# Single-Phase-Energy-Meter_v1_3-rev2.net
KiCad netlist of a schematic drawn in EAGLE
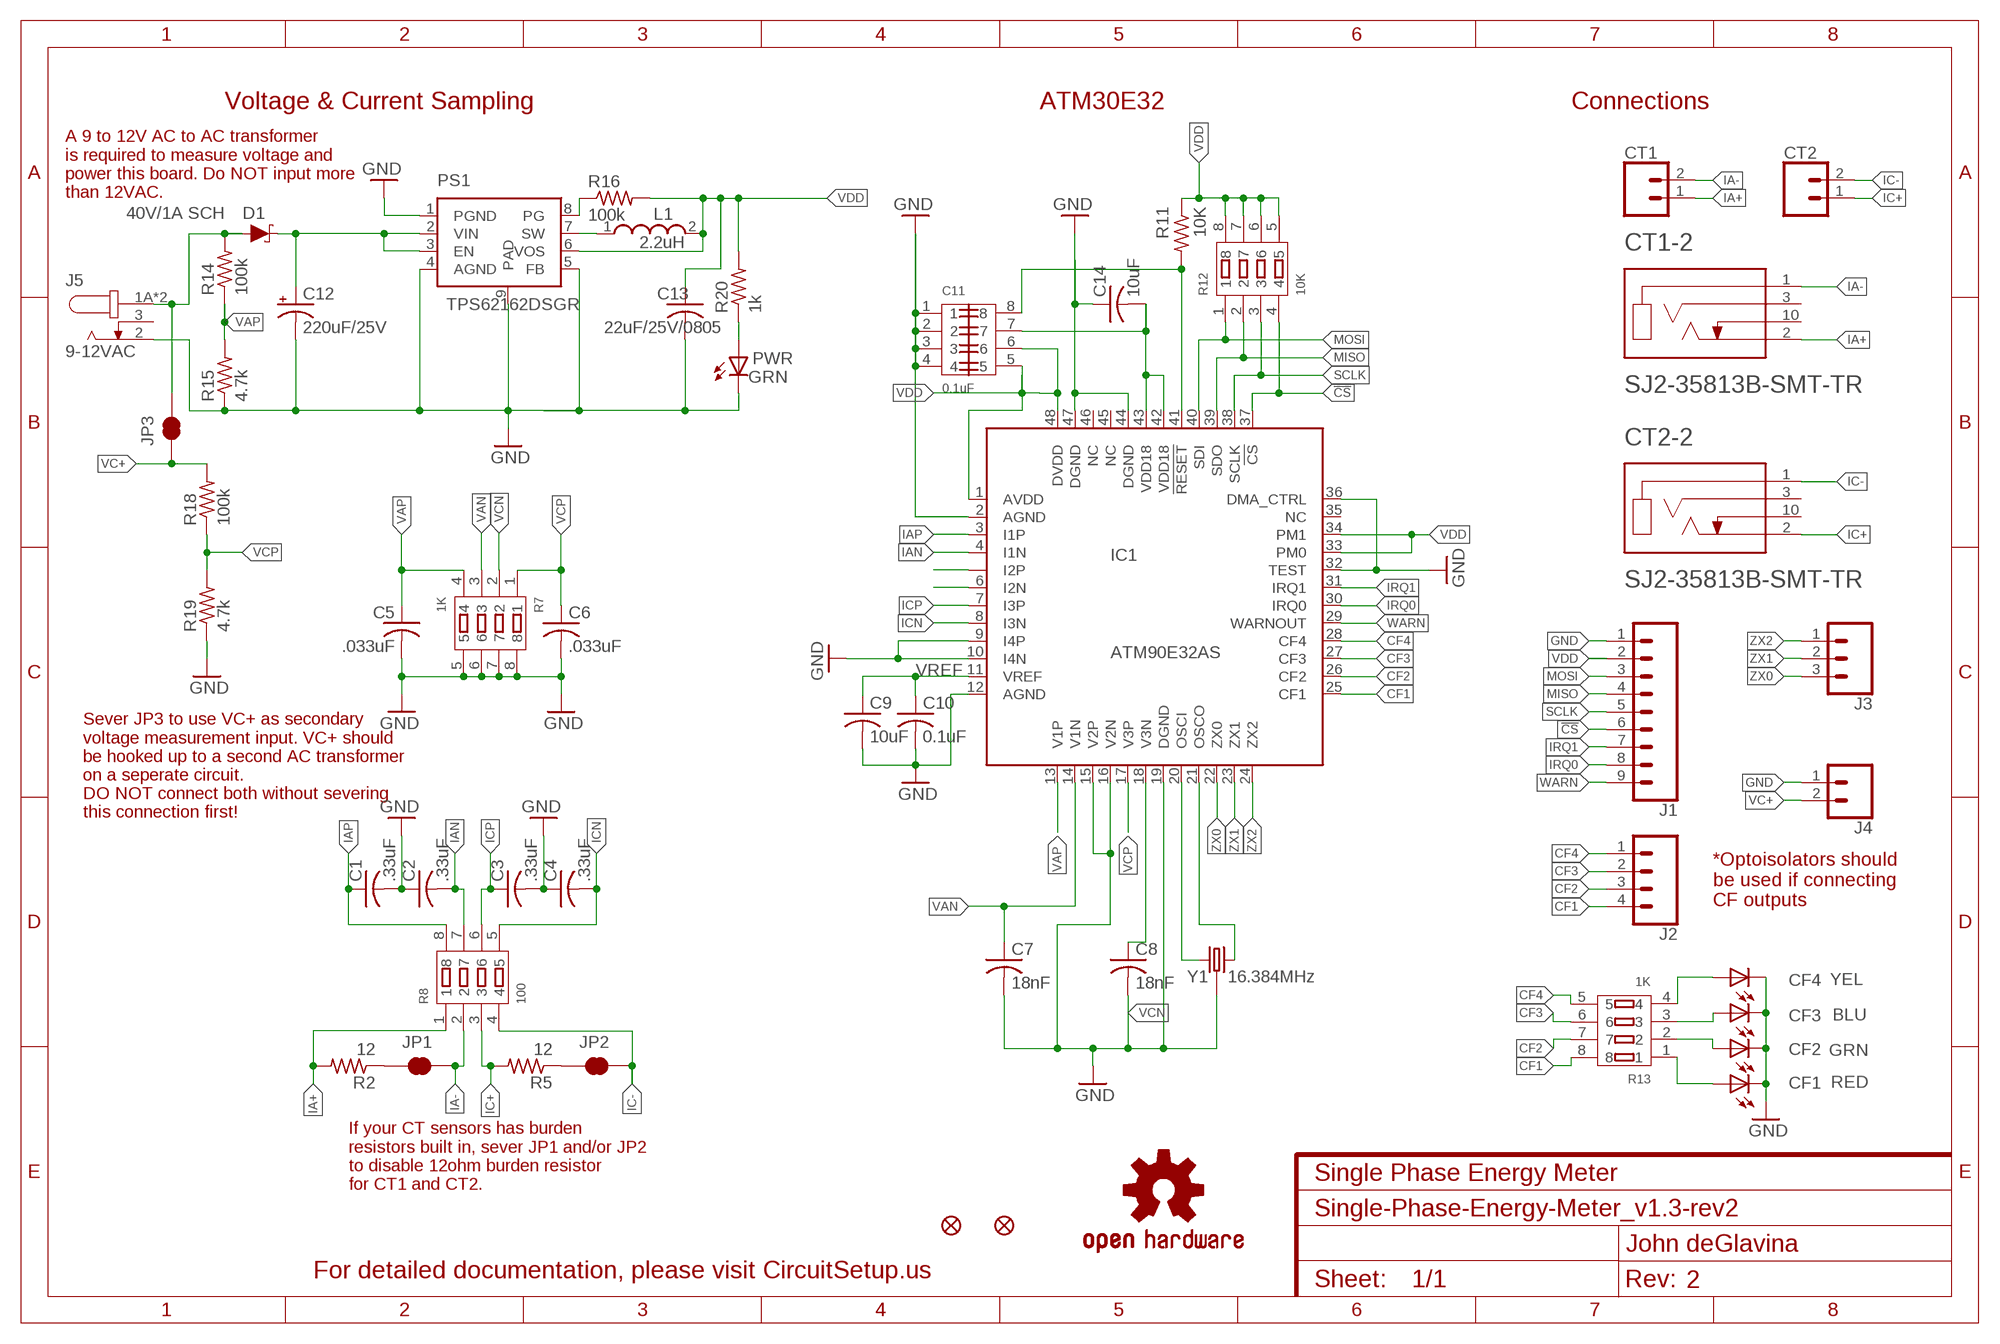
[diagram p0: schematic, sheet 1]

(export (version "E")
  (design (tool "Eeschema 10.0.6"))
  (components
    (comp (ref "C1")
      (value ".33uF")
      (footprint "eagle-import:C0603")
      (libsource (lib "eagle-import") (part "C-USC0603"))
    )
    (comp (ref "C2")
      (value ".33uF")
      (footprint "eagle-import:C0603")
      (libsource (lib "eagle-import") (part "C-USC0603"))
    )
    (comp (ref "C3")
      (value ".33uF")
      (footprint "eagle-import:C0603")
      (libsource (lib "eagle-import") (part "C-USC0603"))
    )
    (comp (ref "C4")
      (value ".33uF")
      (footprint "eagle-import:C0603")
      (libsource (lib "eagle-import") (part "C-USC0603"))
    )
    (comp (ref "C5")
      (value ".033uF")
      (footprint "eagle-import:C0603")
      (libsource (lib "eagle-import") (part "C-USC0603"))
    )
    (comp (ref "C6")
      (value ".033uF")
      (footprint "eagle-import:C0603")
      (libsource (lib "eagle-import") (part "C-USC0603"))
    )
    (comp (ref "C7")
      (value "18nF")
      (footprint "eagle-import:C0603")
      (libsource (lib "eagle-import") (part "C-USC0603"))
    )
    (comp (ref "C8")
      (value "18nF")
      (footprint "eagle-import:C0603")
      (libsource (lib "eagle-import") (part "C-USC0603"))
    )
    (comp (ref "C9")
      (value "10uF")
      (footprint "eagle-import:C0603")
      (libsource (lib "eagle-import") (part "C-USC0603"))
    )
    (comp (ref "C10")
      (value "0.1uF")
      (footprint "eagle-import:C0603")
      (libsource (lib "eagle-import") (part "C-USC0603"))
    )
    (comp (ref "C11")
      (value "0.1uF")
      (footprint "eagle-import:CAPCAF80P320X160X70-8")
      (libsource (lib "eagle-import") (part "CAP-ARRAY4"))
    )
    (comp (ref "C12")
      (value "220uF/25V")
      (footprint "eagle-import:153CLV-0605")
      (libsource (lib "eagle-import") (part "CPOL-US153CLV-0605"))
    )
    (comp (ref "C13")
      (value "22uF/25V/0805")
      (footprint "eagle-import:C0805")
      (libsource (lib "eagle-import") (part "C-USC0805"))
    )
    (comp (ref "C14")
      (value "10uF")
      (footprint "eagle-import:C0603")
      (libsource (lib "eagle-import") (part "C-USC0603"))
    )
    (comp (ref "CF1")
      (value "RED")
      (footprint "eagle-import:CHIP-LED0603")
      (libsource (lib "eagle-import") (part "LEDCHIP-LED0603"))
    )
    (comp (ref "CF2")
      (value "GRN")
      (footprint "eagle-import:CHIP-LED0603")
      (libsource (lib "eagle-import") (part "LEDCHIP-LED0603"))
    )
    (comp (ref "CF3")
      (value "BLU")
      (footprint "eagle-import:CHIP-LED0603")
      (libsource (lib "eagle-import") (part "LEDCHIP-LED0603"))
    )
    (comp (ref "CF4")
      (value "YEL")
      (footprint "eagle-import:CHIP-LED0603")
      (libsource (lib "eagle-import") (part "LEDCHIP-LED0603"))
    )
    (comp (ref "CT1")
      (value "CONN_023.5MM")
      (footprint "eagle-import:SCREWTERMINAL-3.5MM-2")
      (libsource (lib "eagle-import") (part "CONN_023.5MM"))
    )
    (comp (ref "CT1-2")
      (value "SJ2-35813B-SMT-TR")
      (footprint "eagle-import:CUI_SJ2-35813B-SMT-TR")
      (fields (field (name "MANUFACTURER") "CUI"))
      (libsource (lib "eagle-import") (part "SJ2-35813B-SMT-TR"))
    )
    (comp (ref "CT2")
      (value "CONN_023.5MM")
      (footprint "eagle-import:SCREWTERMINAL-3.5MM-2")
      (libsource (lib "eagle-import") (part "CONN_023.5MM"))
    )
    (comp (ref "CT2-2")
      (value "SJ2-35813B-SMT-TR")
      (footprint "eagle-import:CUI_SJ2-35813B-SMT-TR")
      (fields (field (name "MANUFACTURER") "CUI"))
      (libsource (lib "eagle-import") (part "SJ2-35813B-SMT-TR"))
    )
    (comp (ref "D1")
      (value "40V/1A SCH")
      (footprint "eagle-import:SMA-DIODE")
      (libsource (lib "eagle-import") (part "DIODE-SCHOTTKY-SS14"))
    )
    (comp (ref "FD1")
      (value "FIDUCIALUFIDUCIAL")
      (footprint "eagle-import:FIDUCIAL-MICRO")
      (libsource (lib "eagle-import") (part "FIDUCIALUFIDUCIAL"))
    )
    (comp (ref "FD2")
      (value "FIDUCIALUFIDUCIAL")
      (footprint "eagle-import:FIDUCIAL-MICRO")
      (libsource (lib "eagle-import") (part "FIDUCIALUFIDUCIAL"))
    )
    (comp (ref "IC1")
      (value "ATM90E32AS")
      (footprint "eagle-import:QFP50P900X900X120-48N")
      (fields (field (name "SPICEPREFIX") "X"))
      (libsource (lib "eagle-import") (part "ATM90E36"))
    )
    (comp (ref "J1")
      (value "CONN_09")
      (footprint "eagle-import:1X09")
      (libsource (lib "eagle-import") (part "CONN_09"))
    )
    (comp (ref "J2")
      (value "CONN_04")
      (footprint "eagle-import:1X04")
      (libsource (lib "eagle-import") (part "CONN_04"))
    )
    (comp (ref "J3")
      (value "CONN_03")
      (footprint "eagle-import:1X03")
      (libsource (lib "eagle-import") (part "CONN_03"))
    )
    (comp (ref "J4")
      (value "CONN_02")
      (footprint "eagle-import:1X02")
      (libsource (lib "eagle-import") (part "CONN_02"))
    )
    (comp (ref "J5")
      (value "9-12VAC")
      (footprint "eagle-import:CUI_PJ-002AH-SMT-TR")
      (fields (field (name "MF") "CUI") (field (name "MP") "PJ-002AH-SMT-TR"))
      (libsource (lib "eagle-import") (part "PJ-002AH-SMT-TR"))
    )
    (comp (ref "JP1")
      (value "JUMPER-SMT_2_NC_TRACE_SILK")
      (footprint "eagle-import:SMT-JUMPER_2_NC_TRACE_SILK")
      (libsource (lib "eagle-import") (part "JUMPER-SMT_2_NC_TRACE_SILK"))
    )
    (comp (ref "JP2")
      (value "JUMPER-SMT_2_NC_TRACE_SILK")
      (footprint "eagle-import:SMT-JUMPER_2_NC_TRACE_SILK")
      (libsource (lib "eagle-import") (part "JUMPER-SMT_2_NC_TRACE_SILK"))
    )
    (comp (ref "JP3")
      (value "JUMPER-SMT_2_NC_TRACE_SILK")
      (footprint "eagle-import:SMT-JUMPER_2_NC_TRACE_SILK")
      (libsource (lib "eagle-import") (part "JUMPER-SMT_2_NC_TRACE_SILK"))
    )
    (comp (ref "L1")
      (value "2.2uH")
      (footprint "eagle-import:INDPM4042X200N")
      (fields (field (name "ARROW_PART_NUMBER") "PA4332.222NLT"))
      (libsource (lib "eagle-import") (part "PA4332.222NLT"))
    )
    (comp (ref "LOGO1")
      (value "OSHW-LOGOS")
      (footprint "eagle-import:OSHW-LOGO-S")
      (libsource (lib "eagle-import") (part "OSHW-LOGOS"))
    )
    (comp (ref "PS1")
      (value "TPS62162DSGR")
      (footprint "eagle-import:SON50P200X200X80-9N")
      (libsource (lib "eagle-import") (part "TPS62162DSGR"))
    )
    (comp (ref "PWR")
      (value "GRN")
      (footprint "eagle-import:CHIP-LED0603")
      (libsource (lib "eagle-import") (part "LEDCHIP-LED0603"))
    )
    (comp (ref "R2")
      (value "12")
      (footprint "eagle-import:R0603")
      (libsource (lib "eagle-import") (part "R-US_R0603"))
    )
    (comp (ref "R5")
      (value "12")
      (footprint "eagle-import:R0603")
      (libsource (lib "eagle-import") (part "R-US_R0603"))
    )
    (comp (ref "R7")
      (value "1K")
      (footprint "eagle-import:RA1206-8")
      (fields (field (name "MPN") "Chip-Array-Series-1%"))
      (libsource (lib "eagle-import") (part "SMD-RES-ARRAY-1K-4R(RA1206-8)"))
    )
    (comp (ref "R8")
      (value "100")
      (footprint "eagle-import:RA1206-8")
      (fields (field (name "MPN") "Chip-Array-Series-1%"))
      (libsource (lib "eagle-import") (part "SMD-RES-ARRAY-1K-4R(RA1206-8)"))
    )
    (comp (ref "R11")
      (value "10K")
      (footprint "eagle-import:R0603")
      (libsource (lib "eagle-import") (part "R-US_R0603"))
    )
    (comp (ref "R12")
      (value "10K")
      (footprint "eagle-import:RA1206-8")
      (fields (field (name "MPN") "Chip-Array-Series-1%"))
      (libsource (lib "eagle-import") (part "SMD-RES-ARRAY-1K-4R(RA1206-8)"))
    )
    (comp (ref "R13")
      (value "1K")
      (footprint "eagle-import:RA1206-8")
      (fields (field (name "MPN") "Chip-Array-Series-1%"))
      (libsource (lib "eagle-import") (part "SMD-RES-ARRAY-1K-4R(RA1206-8)"))
    )
    (comp (ref "R14")
      (value "100k")
      (footprint "eagle-import:R0603")
      (libsource (lib "eagle-import") (part "R-US_R0603"))
    )
    (comp (ref "R15")
      (value "4.7k")
      (footprint "eagle-import:R0603")
      (libsource (lib "eagle-import") (part "R-US_R0603"))
    )
    (comp (ref "R16")
      (value "100k")
      (footprint "eagle-import:R0603")
      (libsource (lib "eagle-import") (part "R-US_R0603"))
    )
    (comp (ref "R18")
      (value "100k")
      (footprint "eagle-import:R0603")
      (libsource (lib "eagle-import") (part "R-US_R0603"))
    )
    (comp (ref "R19")
      (value "4.7k")
      (footprint "eagle-import:R0603")
      (libsource (lib "eagle-import") (part "R-US_R0603"))
    )
    (comp (ref "R20")
      (value "1k")
      (footprint "eagle-import:R0603")
      (libsource (lib "eagle-import") (part "R-US_R0603"))
    )
    (comp (ref "Y1")
      (value "16.384MHz")
      (footprint "eagle-import:CRYSTAL-SMD-3.2X2.5MM")
      (libsource (lib "eagle-import") (part "CRYSTAL-GROUNDEDSMD-3.2X2.5"))
    )
  )
  (nets
    (net (code "1") (name "/VREF") (class "Default")
      (node (ref "C10") (pin "1") (pinfunction "1_1") (pintype "passive"))
      (node (ref "C9") (pin "1") (pinfunction "1_1") (pintype "passive"))
      (node (ref "IC1") (pin "11") (pinfunction "VREF_11") (pintype "bidirectional"))
    )
    (net (code "2") (name "/~{CS}") (class "Default")
      (node (ref "IC1") (pin "37") (pinfunction "~{CS}_37") (pintype "input"))
      (node (ref "J1") (pin "6") (pinfunction "6_6") (pintype "passive"))
      (node (ref "R12") (pin "4") (pinfunction "4_4") (pintype "bidirectional"))
    )
    (net (code "3") (name "CF1") (class "Default")
      (node (ref "IC1") (pin "25") (pinfunction "CF1_25") (pintype "output"))
      (node (ref "J2") (pin "4") (pinfunction "4_4") (pintype "passive"))
      (node (ref "R13") (pin "8") (pinfunction "8_8") (pintype "bidirectional"))
    )
    (net (code "4") (name "CF2") (class "Default")
      (node (ref "IC1") (pin "26") (pinfunction "CF2_26") (pintype "output"))
      (node (ref "J2") (pin "3") (pinfunction "3_3") (pintype "passive"))
      (node (ref "R13") (pin "7") (pinfunction "7_7") (pintype "bidirectional"))
    )
    (net (code "5") (name "CF3") (class "Default")
      (node (ref "IC1") (pin "27") (pinfunction "CF3_27") (pintype "output"))
      (node (ref "J2") (pin "2") (pinfunction "2_2") (pintype "passive"))
      (node (ref "R13") (pin "6") (pinfunction "6_6") (pintype "bidirectional"))
    )
    (net (code "6") (name "CF4") (class "Default")
      (node (ref "IC1") (pin "28") (pinfunction "CF4_28") (pintype "output"))
      (node (ref "J2") (pin "1") (pinfunction "1_1") (pintype "passive"))
      (node (ref "R13") (pin "5") (pinfunction "5_5") (pintype "bidirectional"))
    )
    (net (code "7") (name "GND") (class "Default")
      (node (ref "C1") (pin "2") (pinfunction "2_2") (pintype "passive"))
      (node (ref "C10") (pin "2") (pinfunction "2_2") (pintype "passive"))
      (node (ref "C11") (pin "1") (pinfunction "1_1") (pintype "bidirectional"))
      (node (ref "C11") (pin "2") (pinfunction "2_2") (pintype "bidirectional"))
      (node (ref "C11") (pin "3") (pinfunction "3_3") (pintype "bidirectional"))
      (node (ref "C11") (pin "4") (pinfunction "4_4") (pintype "bidirectional"))
      (node (ref "C12") (pin "-") (pinfunction "-_-") (pintype "passive"))
      (node (ref "C13") (pin "2") (pinfunction "2_2") (pintype "passive"))
      (node (ref "C14") (pin "1") (pinfunction "1_1") (pintype "passive"))
      (node (ref "C2") (pin "1") (pinfunction "1_1") (pintype "passive"))
      (node (ref "C3") (pin "2") (pinfunction "2_2") (pintype "passive"))
      (node (ref "C4") (pin "1") (pinfunction "1_1") (pintype "passive"))
      (node (ref "C5") (pin "2") (pinfunction "2_2") (pintype "passive"))
      (node (ref "C6") (pin "2") (pinfunction "2_2") (pintype "passive"))
      (node (ref "C7") (pin "2") (pinfunction "2_2") (pintype "passive"))
      (node (ref "C8") (pin "2") (pinfunction "2_2") (pintype "passive"))
      (node (ref "C9") (pin "2") (pinfunction "2_2") (pintype "passive"))
      (node (ref "CF1") (pin "C") (pinfunction "C_C") (pintype "passive"))
      (node (ref "CF2") (pin "C") (pinfunction "C_C") (pintype "passive"))
      (node (ref "CF3") (pin "C") (pinfunction "C_C") (pintype "passive"))
      (node (ref "CF4") (pin "C") (pinfunction "C_C") (pintype "passive"))
      (node (ref "IC1") (pin "10") (pinfunction "I4N_10") (pintype "input"))
      (node (ref "IC1") (pin "12") (pinfunction "AGND_12") (pintype "power_in"))
      (node (ref "IC1") (pin "15") (pinfunction "V2P_15") (pintype "input"))
      (node (ref "IC1") (pin "16") (pinfunction "V2N_16") (pintype "input"))
      (node (ref "IC1") (pin "19") (pinfunction "DGND_19") (pintype "power_in"))
      (node (ref "IC1") (pin "2") (pinfunction "AGND_2") (pintype "power_in"))
      (node (ref "IC1") (pin "32") (pinfunction "TEST_32") (pintype "power_in"))
      (node (ref "IC1") (pin "36") (pinfunction "DMA_CTRL_36") (pintype "input"))
      (node (ref "IC1") (pin "44") (pinfunction "DGND_44") (pintype "power_in"))
      (node (ref "IC1") (pin "47") (pinfunction "DGND_47") (pintype "power_in"))
      (node (ref "IC1") (pin "9") (pinfunction "I4P_9") (pintype "input"))
      (node (ref "J1") (pin "1") (pinfunction "1_1") (pintype "passive"))
      (node (ref "J4") (pin "1") (pinfunction "1_1") (pintype "passive"))
      (node (ref "J5") (pin "2") (pinfunction "2_2") (pintype "passive"))
      (node (ref "PS1") (pin "1") (pinfunction "PGND_1") (pintype "power_in"))
      (node (ref "PS1") (pin "4") (pinfunction "AGND_4") (pintype "power_in"))
      (node (ref "PS1") (pin "5") (pinfunction "FB_5") (pintype "input"))
      (node (ref "PS1") (pin "9") (pinfunction "PAD_9") (pintype "power_in"))
      (node (ref "PWR") (pin "C") (pinfunction "C_C") (pintype "passive"))
      (node (ref "R15") (pin "1") (pinfunction "1_1") (pintype "passive"))
      (node (ref "R19") (pin "1") (pinfunction "1_1") (pintype "passive"))
      (node (ref "R7") (pin "5") (pinfunction "5_5") (pintype "bidirectional"))
      (node (ref "R7") (pin "6") (pinfunction "6_6") (pintype "bidirectional"))
      (node (ref "R7") (pin "7") (pinfunction "7_7") (pintype "bidirectional"))
      (node (ref "R7") (pin "8") (pinfunction "8_8") (pintype "bidirectional"))
      (node (ref "Y1") (pin "2") (pinfunction "3_2") (pintype "passive"))
      (node (ref "Y1") (pin "4") (pinfunction "3_4") (pintype "passive"))
    )
    (net (code "8") (name "IA+") (class "Default")
      (node (ref "CT1") (pin "1") (pinfunction "1_1") (pintype "passive"))
      (node (ref "CT1-2") (pin "2") (pinfunction "TIP_2") (pintype "passive"))
      (node (ref "R2") (pin "2") (pinfunction "2_2") (pintype "passive"))
      (node (ref "R8") (pin "1") (pinfunction "1_1") (pintype "bidirectional"))
    )
    (net (code "9") (name "IA-") (class "Default")
      (node (ref "CT1") (pin "2") (pinfunction "2_2") (pintype "passive"))
      (node (ref "CT1-2") (pin "1") (pinfunction "SLEEVE_1") (pintype "passive"))
      (node (ref "JP1") (pin "2") (pinfunction "2_2") (pintype "passive"))
      (node (ref "R8") (pin "2") (pinfunction "2_2") (pintype "bidirectional"))
    )
    (net (code "10") (name "IAN") (class "Default")
      (node (ref "C2") (pin "2") (pinfunction "2_2") (pintype "passive"))
      (node (ref "IC1") (pin "4") (pinfunction "I1N_4") (pintype "input"))
      (node (ref "R8") (pin "7") (pinfunction "7_7") (pintype "bidirectional"))
    )
    (net (code "11") (name "IAP") (class "Default")
      (node (ref "C1") (pin "1") (pinfunction "1_1") (pintype "passive"))
      (node (ref "IC1") (pin "3") (pinfunction "I1P_3") (pintype "input"))
      (node (ref "R8") (pin "8") (pinfunction "8_8") (pintype "bidirectional"))
    )
    (net (code "12") (name "IC+") (class "Default")
      (node (ref "CT2") (pin "1") (pinfunction "1_1") (pintype "passive"))
      (node (ref "CT2-2") (pin "2") (pinfunction "TIP_2") (pintype "passive"))
      (node (ref "R5") (pin "2") (pinfunction "2_2") (pintype "passive"))
      (node (ref "R8") (pin "3") (pinfunction "3_3") (pintype "bidirectional"))
    )
    (net (code "13") (name "IC-") (class "Default")
      (node (ref "CT2") (pin "2") (pinfunction "2_2") (pintype "passive"))
      (node (ref "CT2-2") (pin "1") (pinfunction "SLEEVE_1") (pintype "passive"))
      (node (ref "JP2") (pin "2") (pinfunction "2_2") (pintype "passive"))
      (node (ref "R8") (pin "4") (pinfunction "4_4") (pintype "bidirectional"))
    )
    (net (code "14") (name "ICN") (class "Default")
      (node (ref "C4") (pin "2") (pinfunction "2_2") (pintype "passive"))
      (node (ref "IC1") (pin "8") (pinfunction "I3N_8") (pintype "input"))
      (node (ref "R8") (pin "5") (pinfunction "5_5") (pintype "bidirectional"))
    )
    (net (code "15") (name "ICP") (class "Default")
      (node (ref "C3") (pin "1") (pinfunction "1_1") (pintype "passive"))
      (node (ref "IC1") (pin "7") (pinfunction "I3P_7") (pintype "input"))
      (node (ref "R8") (pin "6") (pinfunction "6_6") (pintype "bidirectional"))
    )
    (net (code "16") (name "IRQ0") (class "Default")
      (node (ref "IC1") (pin "30") (pinfunction "IRQ0_30") (pintype "output"))
      (node (ref "J1") (pin "8") (pinfunction "8_8") (pintype "passive"))
    )
    (net (code "17") (name "IRQ1") (class "Default")
      (node (ref "IC1") (pin "31") (pinfunction "IRQ1_31") (pintype "output"))
      (node (ref "J1") (pin "7") (pinfunction "7_7") (pintype "passive"))
    )
    (net (code "18") (name "MISO") (class "Default")
      (node (ref "IC1") (pin "39") (pinfunction "SDO_39") (pintype "output"))
      (node (ref "J1") (pin "4") (pinfunction "4_4") (pintype "passive"))
      (node (ref "R12") (pin "2") (pinfunction "2_2") (pintype "bidirectional"))
    )
    (net (code "19") (name "MOSI") (class "Default")
      (node (ref "IC1") (pin "40") (pinfunction "SDI_40") (pintype "input"))
      (node (ref "J1") (pin "3") (pinfunction "3_3") (pintype "passive"))
      (node (ref "R12") (pin "1") (pinfunction "1_1") (pintype "bidirectional"))
    )
    (net (code "20") (name "Net-(C11-Pad7)") (class "Default")
      (node (ref "C11") (pin "7") (pinfunction "7_7") (pintype "bidirectional"))
      (node (ref "C14") (pin "2") (pinfunction "2_2") (pintype "passive"))
      (node (ref "IC1") (pin "42") (pinfunction "VDD18_42") (pintype "power_in"))
      (node (ref "IC1") (pin "43") (pinfunction "VDD18_43") (pintype "power_in"))
    )
    (net (code "21") (name "Net-(CF1-PadA)") (class "Default")
      (node (ref "CF1") (pin "A") (pinfunction "A_A") (pintype "passive"))
      (node (ref "R13") (pin "1") (pinfunction "1_1") (pintype "bidirectional"))
    )
    (net (code "22") (name "Net-(CF2-PadA)") (class "Default")
      (node (ref "CF2") (pin "A") (pinfunction "A_A") (pintype "passive"))
      (node (ref "R13") (pin "2") (pinfunction "2_2") (pintype "bidirectional"))
    )
    (net (code "23") (name "Net-(CF3-PadA)") (class "Default")
      (node (ref "CF3") (pin "A") (pinfunction "A_A") (pintype "passive"))
      (node (ref "R13") (pin "3") (pinfunction "3_3") (pintype "bidirectional"))
    )
    (net (code "24") (name "Net-(CF4-PadA)") (class "Default")
      (node (ref "CF4") (pin "A") (pinfunction "A_A") (pintype "passive"))
      (node (ref "R13") (pin "4") (pinfunction "4_4") (pintype "bidirectional"))
    )
    (net (code "25") (name "Net-(D1-PadA)") (class "Default")
      (node (ref "D1") (pin "A") (pinfunction "A_A") (pintype "passive"))
      (node (ref "J5") (pin "1A") (pinfunction "1_1A") (pintype "passive"))
      (node (ref "J5") (pin "1B") (pinfunction "1_1B") (pintype "passive"))
      (node (ref "JP3") (pin "2") (pinfunction "2_2") (pintype "passive"))
      (node (ref "R14") (pin "2") (pinfunction "2_2") (pintype "passive"))
    )
    (net (code "26") (name "Net-(IC1-OSCI)") (class "Default")
      (node (ref "IC1") (pin "20") (pinfunction "OSCI_20") (pintype "input"))
      (node (ref "Y1") (pin "1") (pinfunction "1_1") (pintype "passive"))
    )
    (net (code "27") (name "Net-(IC1-OSCO)") (class "Default")
      (node (ref "IC1") (pin "21") (pinfunction "OSCO_21") (pintype "output"))
      (node (ref "Y1") (pin "3") (pinfunction "2_3") (pintype "passive"))
    )
    (net (code "28") (name "Net-(IC1-~{RESET})") (class "Default")
      (node (ref "C11") (pin "8") (pinfunction "8_8") (pintype "bidirectional"))
      (node (ref "IC1") (pin "41") (pinfunction "~{RESET}_41") (pintype "input"))
      (node (ref "R11") (pin "2") (pinfunction "2_2") (pintype "passive"))
    )
    (net (code "29") (name "Net-(JP1-Pad1)") (class "Default")
      (node (ref "JP1") (pin "1") (pinfunction "1_1") (pintype "passive"))
      (node (ref "R2") (pin "1") (pinfunction "1_1") (pintype "passive"))
    )
    (net (code "30") (name "Net-(JP2-Pad1)") (class "Default")
      (node (ref "JP2") (pin "1") (pinfunction "1_1") (pintype "passive"))
      (node (ref "R5") (pin "1") (pinfunction "1_1") (pintype "passive"))
    )
    (net (code "31") (name "Net-(PS1-EN)") (class "Default")
      (node (ref "C12") (pin "+") (pinfunction "+_+") (pintype "passive"))
      (node (ref "D1") (pin "C") (pinfunction "C_C") (pintype "passive"))
      (node (ref "PS1") (pin "2") (pinfunction "VIN_2") (pintype "power_in"))
      (node (ref "PS1") (pin "3") (pinfunction "EN_3") (pintype "input"))
    )
    (net (code "32") (name "Net-(PS1-PG)") (class "Default")
      (node (ref "PS1") (pin "8") (pinfunction "PG_8") (pintype "power_in"))
      (node (ref "R16") (pin "1") (pinfunction "1_1") (pintype "passive"))
    )
    (net (code "33") (name "Net-(PS1-SW)") (class "Default")
      (node (ref "L1") (pin "1") (pinfunction "1_1") (pintype "bidirectional"))
      (node (ref "PS1") (pin "7") (pinfunction "SW_7") (pintype "output"))
    )
    (net (code "34") (name "Net-(PWR-PadA)") (class "Default")
      (node (ref "PWR") (pin "A") (pinfunction "A_A") (pintype "passive"))
      (node (ref "R20") (pin "1") (pinfunction "1_1") (pintype "passive"))
    )
    (net (code "35") (name "SCLK") (class "Default")
      (node (ref "IC1") (pin "38") (pinfunction "SCLK_38") (pintype "input"))
      (node (ref "J1") (pin "5") (pinfunction "5_5") (pintype "passive"))
      (node (ref "R12") (pin "3") (pinfunction "3_3") (pintype "bidirectional"))
    )
    (net (code "36") (name "VAN") (class "Default")
      (node (ref "C7") (pin "1") (pinfunction "1_1") (pintype "passive"))
      (node (ref "IC1") (pin "14") (pinfunction "V1N_14") (pintype "input"))
      (node (ref "R7") (pin "3") (pinfunction "3_3") (pintype "bidirectional"))
    )
    (net (code "37") (name "VAP") (class "Default")
      (node (ref "C5") (pin "1") (pinfunction "1_1") (pintype "passive"))
      (node (ref "IC1") (pin "13") (pinfunction "V1P_13") (pintype "input"))
      (node (ref "R14") (pin "1") (pinfunction "1_1") (pintype "passive"))
      (node (ref "R15") (pin "2") (pinfunction "2_2") (pintype "passive"))
      (node (ref "R7") (pin "4") (pinfunction "4_4") (pintype "bidirectional"))
    )
    (net (code "38") (name "VC+") (class "Default")
      (node (ref "J4") (pin "2") (pinfunction "2_2") (pintype "passive"))
      (node (ref "JP3") (pin "1") (pinfunction "1_1") (pintype "passive"))
      (node (ref "R18") (pin "2") (pinfunction "2_2") (pintype "passive"))
    )
    (net (code "39") (name "VCN") (class "Default")
      (node (ref "C8") (pin "1") (pinfunction "1_1") (pintype "passive"))
      (node (ref "IC1") (pin "18") (pinfunction "V3N_18") (pintype "input"))
      (node (ref "R7") (pin "2") (pinfunction "2_2") (pintype "bidirectional"))
    )
    (net (code "40") (name "VCP") (class "Default")
      (node (ref "C6") (pin "1") (pinfunction "1_1") (pintype "passive"))
      (node (ref "IC1") (pin "17") (pinfunction "V3P_17") (pintype "input"))
      (node (ref "R18") (pin "1") (pinfunction "1_1") (pintype "passive"))
      (node (ref "R19") (pin "2") (pinfunction "2_2") (pintype "passive"))
      (node (ref "R7") (pin "1") (pinfunction "1_1") (pintype "bidirectional"))
    )
    (net (code "41") (name "VDD") (class "Default")
      (node (ref "C11") (pin "5") (pinfunction "5_5") (pintype "bidirectional"))
      (node (ref "C11") (pin "6") (pinfunction "6_6") (pintype "bidirectional"))
      (node (ref "C13") (pin "1") (pinfunction "1_1") (pintype "passive"))
      (node (ref "IC1") (pin "1") (pinfunction "AVDD_1") (pintype "power_in"))
      (node (ref "IC1") (pin "33") (pinfunction "PM0_33") (pintype "input"))
      (node (ref "IC1") (pin "34") (pinfunction "PM1_34") (pintype "input"))
      (node (ref "IC1") (pin "48") (pinfunction "DVDD_48") (pintype "power_in"))
      (node (ref "J1") (pin "2") (pinfunction "2_2") (pintype "passive"))
      (node (ref "L1") (pin "2") (pinfunction "2_2") (pintype "bidirectional"))
      (node (ref "PS1") (pin "6") (pinfunction "VOS_6") (pintype "input"))
      (node (ref "R11") (pin "1") (pinfunction "1_1") (pintype "passive"))
      (node (ref "R12") (pin "5") (pinfunction "5_5") (pintype "bidirectional"))
      (node (ref "R12") (pin "6") (pinfunction "6_6") (pintype "bidirectional"))
      (node (ref "R12") (pin "7") (pinfunction "7_7") (pintype "bidirectional"))
      (node (ref "R12") (pin "8") (pinfunction "8_8") (pintype "bidirectional"))
      (node (ref "R16") (pin "2") (pinfunction "2_2") (pintype "passive"))
      (node (ref "R20") (pin "2") (pinfunction "2_2") (pintype "passive"))
    )
    (net (code "42") (name "WARN") (class "Default")
      (node (ref "IC1") (pin "29") (pinfunction "WARNOUT_29") (pintype "output"))
      (node (ref "J1") (pin "9") (pinfunction "9_9") (pintype "passive"))
    )
    (net (code "43") (name "ZX0") (class "Default")
      (node (ref "IC1") (pin "22") (pinfunction "ZX0_22") (pintype "output"))
      (node (ref "J3") (pin "3") (pinfunction "3_3") (pintype "passive"))
    )
    (net (code "44") (name "ZX1") (class "Default")
      (node (ref "IC1") (pin "23") (pinfunction "ZX1_23") (pintype "output"))
      (node (ref "J3") (pin "2") (pinfunction "2_2") (pintype "passive"))
    )
    (net (code "45") (name "ZX2") (class "Default")
      (node (ref "IC1") (pin "24") (pinfunction "ZX2_24") (pintype "output"))
      (node (ref "J3") (pin "1") (pinfunction "1_1") (pintype "passive"))
    )
    (net (code "46") (name "unconnected-(CT1-2-RING-Pad3)") (class "Default")
      (node (ref "CT1-2") (pin "3") (pinfunction "RING_3") (pintype "passive"))
    )
    (net (code "47") (name "unconnected-(CT1-2-TIP_SWITCH-Pad10)") (class "Default")
      (node (ref "CT1-2") (pin "10") (pinfunction "TIP_SWITCH_10") (pintype "passive"))
    )
    (net (code "48") (name "unconnected-(CT2-2-RING-Pad3)") (class "Default")
      (node (ref "CT2-2") (pin "3") (pinfunction "RING_3") (pintype "passive"))
    )
    (net (code "49") (name "unconnected-(CT2-2-TIP_SWITCH-Pad10)") (class "Default")
      (node (ref "CT2-2") (pin "10") (pinfunction "TIP_SWITCH_10") (pintype "passive"))
    )
    (net (code "50") (name "unconnected-(IC1-I2N-Pad6)") (class "Default")
      (node (ref "IC1") (pin "6") (pinfunction "I2N_6") (pintype "input"))
    )
    (net (code "51") (name "unconnected-(IC1-I2P-Pad5)") (class "Default")
      (node (ref "IC1") (pin "5") (pinfunction "I2P_5") (pintype "input"))
    )
    (net (code "52") (name "unconnected-(IC1-NC-Pad35)") (class "Default")
      (node (ref "IC1") (pin "35") (pinfunction "NC_35") (pintype "no_connect"))
    )
    (net (code "53") (name "unconnected-(IC1-NC-Pad45)") (class "Default")
      (node (ref "IC1") (pin "45") (pinfunction "NC_45") (pintype "no_connect"))
    )
    (net (code "54") (name "unconnected-(IC1-NC-Pad46)") (class "Default")
      (node (ref "IC1") (pin "46") (pinfunction "NC_46") (pintype "no_connect"))
    )
    (net (code "55") (name "unconnected-(J5-Pad3)") (class "Default")
      (node (ref "J5") (pin "3") (pinfunction "3_3") (pintype "passive"))
    )
  )
)
